# M900X.net
KiCad netlist of a schematic drawn in EAGLE
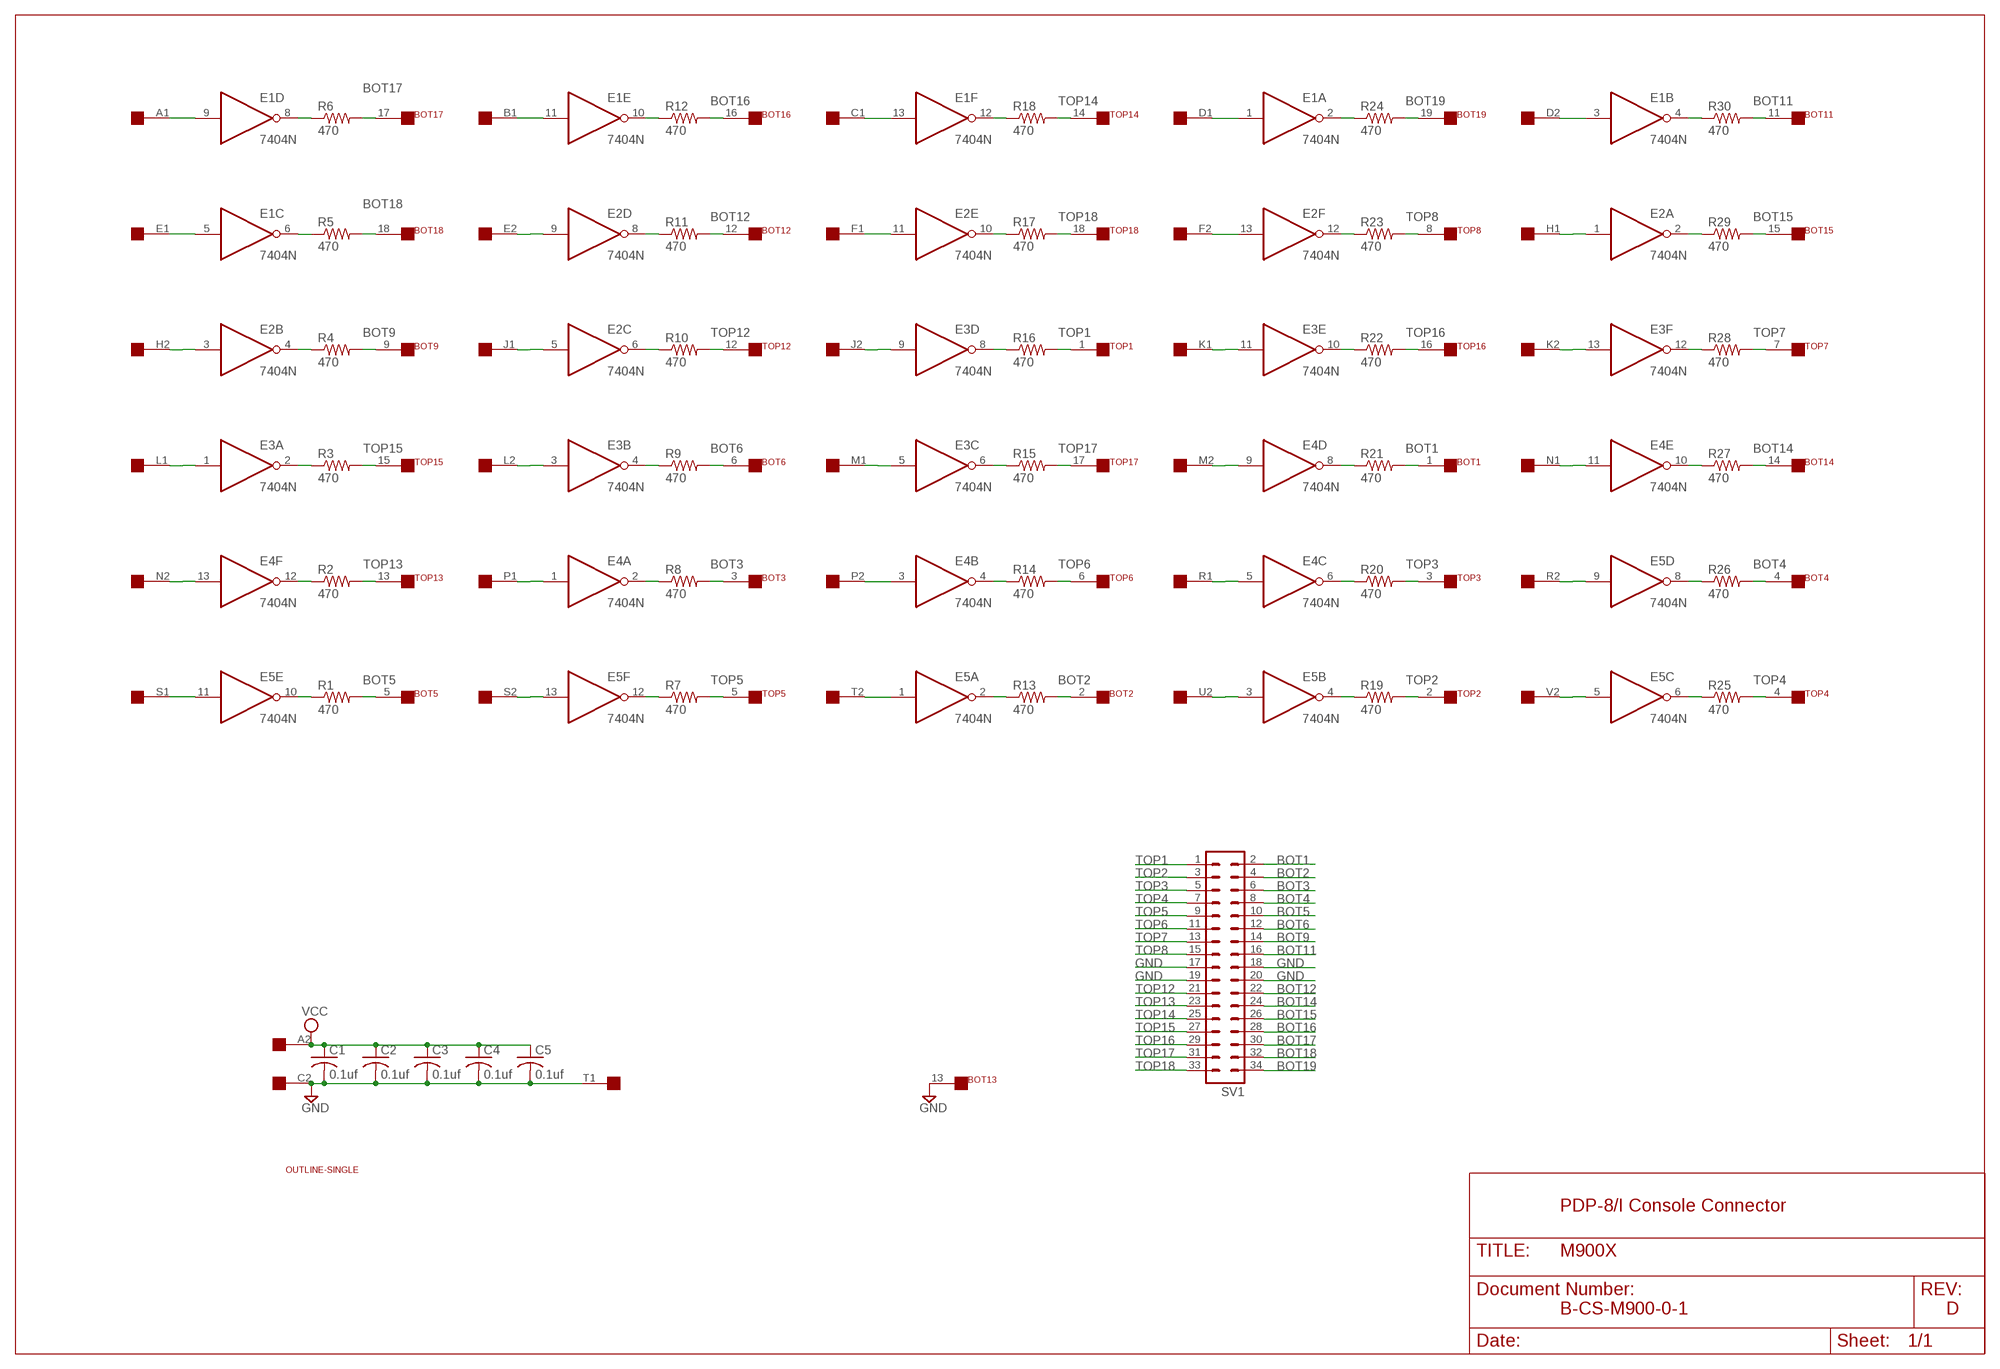
[diagram p0: schematic, sheet 1]

(export (version "E")
  (design (tool "Eeschema 10.0.6"))
  (components
    (comp (ref "BOT")
      (value "FLEX19")
      (footprint "eagle-import:FLEX19")
      (libsource (lib "eagle-import") (part "FLEX19"))
    )
    (comp (ref "C1")
      (value "0.1uf")
      (footprint "eagle-import:C050-025X075")
      (libsource (lib "eagle-import") (part "C-US050-025X075"))
    )
    (comp (ref "C2")
      (value "0.1uf")
      (footprint "eagle-import:C050-025X075")
      (libsource (lib "eagle-import") (part "C-US050-025X075"))
    )
    (comp (ref "C3")
      (value "0.1uf")
      (footprint "eagle-import:C050-025X075")
      (libsource (lib "eagle-import") (part "C-US050-025X075"))
    )
    (comp (ref "C4")
      (value "0.1uf")
      (footprint "eagle-import:C050-025X075")
      (libsource (lib "eagle-import") (part "C-US050-025X075"))
    )
    (comp (ref "C5")
      (value "0.1uf")
      (footprint "eagle-import:C050-025X075")
      (libsource (lib "eagle-import") (part "C-US050-025X075"))
    )
    (comp (ref "E1")
      (value "7404N")
      (footprint "eagle-import:DIL14")
      (libsource (lib "eagle-import") (part "7404N"))
    )
    (comp (ref "E2")
      (value "7404N")
      (footprint "eagle-import:DIL14")
      (libsource (lib "eagle-import") (part "7404N"))
    )
    (comp (ref "E3")
      (value "7404N")
      (footprint "eagle-import:DIL14")
      (libsource (lib "eagle-import") (part "7404N"))
    )
    (comp (ref "E4")
      (value "7404N")
      (footprint "eagle-import:DIL14")
      (libsource (lib "eagle-import") (part "7404N"))
    )
    (comp (ref "E5")
      (value "7404N")
      (footprint "eagle-import:DIL14")
      (libsource (lib "eagle-import") (part "7404N"))
    )
    (comp (ref "EDGE")
      (value "SINGLE")
      (footprint "eagle-import:EDGE-CON2")
      (libsource (lib "eagle-import") (part "SINGLE"))
    )
    (comp (ref "R1")
      (value "470")
      (footprint "eagle-import:0207_10")
      (libsource (lib "eagle-import") (part "R-US_0207/10"))
    )
    (comp (ref "R2")
      (value "470")
      (footprint "eagle-import:0207_10")
      (libsource (lib "eagle-import") (part "R-US_0207/10"))
    )
    (comp (ref "R3")
      (value "470")
      (footprint "eagle-import:0207_10")
      (libsource (lib "eagle-import") (part "R-US_0207/10"))
    )
    (comp (ref "R4")
      (value "470")
      (footprint "eagle-import:0207_10")
      (libsource (lib "eagle-import") (part "R-US_0207/10"))
    )
    (comp (ref "R5")
      (value "470")
      (footprint "eagle-import:0207_10")
      (libsource (lib "eagle-import") (part "R-US_0207/10"))
    )
    (comp (ref "R6")
      (value "470")
      (footprint "eagle-import:0207_10")
      (libsource (lib "eagle-import") (part "R-US_0207/10"))
    )
    (comp (ref "R7")
      (value "470")
      (footprint "eagle-import:0207_10")
      (libsource (lib "eagle-import") (part "R-US_0207/10"))
    )
    (comp (ref "R8")
      (value "470")
      (footprint "eagle-import:0207_10")
      (libsource (lib "eagle-import") (part "R-US_0207/10"))
    )
    (comp (ref "R9")
      (value "470")
      (footprint "eagle-import:0207_10")
      (libsource (lib "eagle-import") (part "R-US_0207/10"))
    )
    (comp (ref "R10")
      (value "470")
      (footprint "eagle-import:0207_10")
      (libsource (lib "eagle-import") (part "R-US_0207/10"))
    )
    (comp (ref "R11")
      (value "470")
      (footprint "eagle-import:0207_10")
      (libsource (lib "eagle-import") (part "R-US_0207/10"))
    )
    (comp (ref "R12")
      (value "470")
      (footprint "eagle-import:0207_10")
      (libsource (lib "eagle-import") (part "R-US_0207/10"))
    )
    (comp (ref "R13")
      (value "470")
      (footprint "eagle-import:0207_10")
      (libsource (lib "eagle-import") (part "R-US_0207/10"))
    )
    (comp (ref "R14")
      (value "470")
      (footprint "eagle-import:0207_10")
      (libsource (lib "eagle-import") (part "R-US_0207/10"))
    )
    (comp (ref "R15")
      (value "470")
      (footprint "eagle-import:0207_10")
      (libsource (lib "eagle-import") (part "R-US_0207/10"))
    )
    (comp (ref "R16")
      (value "470")
      (footprint "eagle-import:0207_10")
      (libsource (lib "eagle-import") (part "R-US_0207/10"))
    )
    (comp (ref "R17")
      (value "470")
      (footprint "eagle-import:0207_10")
      (libsource (lib "eagle-import") (part "R-US_0207/10"))
    )
    (comp (ref "R18")
      (value "470")
      (footprint "eagle-import:0207_10")
      (libsource (lib "eagle-import") (part "R-US_0207/10"))
    )
    (comp (ref "R19")
      (value "470")
      (footprint "eagle-import:0207_10")
      (libsource (lib "eagle-import") (part "R-US_0207/10"))
    )
    (comp (ref "R20")
      (value "470")
      (footprint "eagle-import:0207_10")
      (libsource (lib "eagle-import") (part "R-US_0207/10"))
    )
    (comp (ref "R21")
      (value "470")
      (footprint "eagle-import:0207_10")
      (libsource (lib "eagle-import") (part "R-US_0207/10"))
    )
    (comp (ref "R22")
      (value "470")
      (footprint "eagle-import:0207_10")
      (libsource (lib "eagle-import") (part "R-US_0207/10"))
    )
    (comp (ref "R23")
      (value "470")
      (footprint "eagle-import:0207_10")
      (libsource (lib "eagle-import") (part "R-US_0207/10"))
    )
    (comp (ref "R24")
      (value "470")
      (footprint "eagle-import:0207_10")
      (libsource (lib "eagle-import") (part "R-US_0207/10"))
    )
    (comp (ref "R25")
      (value "470")
      (footprint "eagle-import:0207_10")
      (libsource (lib "eagle-import") (part "R-US_0207/10"))
    )
    (comp (ref "R26")
      (value "470")
      (footprint "eagle-import:0207_10")
      (libsource (lib "eagle-import") (part "R-US_0207/10"))
    )
    (comp (ref "R27")
      (value "470")
      (footprint "eagle-import:0207_10")
      (libsource (lib "eagle-import") (part "R-US_0207/10"))
    )
    (comp (ref "R28")
      (value "470")
      (footprint "eagle-import:0207_10")
      (libsource (lib "eagle-import") (part "R-US_0207/10"))
    )
    (comp (ref "R29")
      (value "470")
      (footprint "eagle-import:0207_10")
      (libsource (lib "eagle-import") (part "R-US_0207/10"))
    )
    (comp (ref "R30")
      (value "470")
      (footprint "eagle-import:0207_10")
      (libsource (lib "eagle-import") (part "R-US_0207/10"))
    )
    (comp (ref "SV1")
      (value "ML34L")
      (footprint "eagle-import:ML34L")
      (libsource (lib "eagle-import") (part "ML34L"))
    )
    (comp (ref "TOP")
      (value "FLEX19")
      (footprint "eagle-import:FLEX19")
      (libsource (lib "eagle-import") (part "FLEX19"))
    )
    (comp (ref "U$2")
      (value "OUTLINE-SINGLE")
      (footprint "eagle-import:SINGLE")
      (libsource (lib "eagle-import") (part "OUTLINE-SINGLE"))
    )
  )
  (nets
    (net (code "1") (name "/BOT1") (class "Default")
      (node (ref "BOT") (pin "1") (pinfunction "1_1") (pintype "passive"))
      (node (ref "R21") (pin "2") (pinfunction "2_2") (pintype "passive"))
      (node (ref "SV1") (pin "2") (pinfunction "2_2") (pintype "passive"))
    )
    (net (code "2") (name "/BOT2") (class "Default")
      (node (ref "BOT") (pin "2") (pinfunction "1_2") (pintype "passive"))
      (node (ref "R13") (pin "2") (pinfunction "2_2") (pintype "passive"))
      (node (ref "SV1") (pin "4") (pinfunction "4_4") (pintype "passive"))
    )
    (net (code "3") (name "/BOT3") (class "Default")
      (node (ref "BOT") (pin "3") (pinfunction "1_3") (pintype "passive"))
      (node (ref "R8") (pin "2") (pinfunction "2_2") (pintype "passive"))
      (node (ref "SV1") (pin "6") (pinfunction "6_6") (pintype "passive"))
    )
    (net (code "4") (name "/BOT4") (class "Default")
      (node (ref "BOT") (pin "4") (pinfunction "1_4") (pintype "passive"))
      (node (ref "R26") (pin "2") (pinfunction "2_2") (pintype "passive"))
      (node (ref "SV1") (pin "8") (pinfunction "8_8") (pintype "passive"))
    )
    (net (code "5") (name "/BOT5") (class "Default")
      (node (ref "BOT") (pin "5") (pinfunction "1_5") (pintype "passive"))
      (node (ref "R1") (pin "2") (pinfunction "2_2") (pintype "passive"))
      (node (ref "SV1") (pin "10") (pinfunction "10_10") (pintype "passive"))
    )
    (net (code "6") (name "/BOT6") (class "Default")
      (node (ref "BOT") (pin "6") (pinfunction "1_6") (pintype "passive"))
      (node (ref "R9") (pin "2") (pinfunction "2_2") (pintype "passive"))
      (node (ref "SV1") (pin "12") (pinfunction "12_12") (pintype "passive"))
    )
    (net (code "7") (name "/BOT9") (class "Default")
      (node (ref "BOT") (pin "9") (pinfunction "1_9") (pintype "passive"))
      (node (ref "R4") (pin "2") (pinfunction "2_2") (pintype "passive"))
      (node (ref "SV1") (pin "14") (pinfunction "14_14") (pintype "passive"))
    )
    (net (code "8") (name "/BOT11") (class "Default")
      (node (ref "BOT") (pin "11") (pinfunction "1_11") (pintype "passive"))
      (node (ref "R30") (pin "2") (pinfunction "2_2") (pintype "passive"))
      (node (ref "SV1") (pin "16") (pinfunction "16_16") (pintype "passive"))
    )
    (net (code "9") (name "/BOT12") (class "Default")
      (node (ref "BOT") (pin "12") (pinfunction "1_12") (pintype "passive"))
      (node (ref "R11") (pin "2") (pinfunction "2_2") (pintype "passive"))
      (node (ref "SV1") (pin "22") (pinfunction "22_22") (pintype "passive"))
    )
    (net (code "10") (name "/BOT14") (class "Default")
      (node (ref "BOT") (pin "14") (pinfunction "1_14") (pintype "passive"))
      (node (ref "R27") (pin "2") (pinfunction "2_2") (pintype "passive"))
      (node (ref "SV1") (pin "24") (pinfunction "24_24") (pintype "passive"))
    )
    (net (code "11") (name "/BOT15") (class "Default")
      (node (ref "BOT") (pin "15") (pinfunction "1_15") (pintype "passive"))
      (node (ref "R29") (pin "2") (pinfunction "2_2") (pintype "passive"))
      (node (ref "SV1") (pin "26") (pinfunction "26_26") (pintype "passive"))
    )
    (net (code "12") (name "/BOT16") (class "Default")
      (node (ref "BOT") (pin "16") (pinfunction "1_16") (pintype "passive"))
      (node (ref "R12") (pin "2") (pinfunction "2_2") (pintype "passive"))
      (node (ref "SV1") (pin "28") (pinfunction "28_28") (pintype "passive"))
    )
    (net (code "13") (name "/BOT17") (class "Default")
      (node (ref "BOT") (pin "17") (pinfunction "1_17") (pintype "passive"))
      (node (ref "R6") (pin "2") (pinfunction "2_2") (pintype "passive"))
      (node (ref "SV1") (pin "30") (pinfunction "30_30") (pintype "passive"))
    )
    (net (code "14") (name "/BOT18") (class "Default")
      (node (ref "BOT") (pin "18") (pinfunction "1_18") (pintype "passive"))
      (node (ref "R5") (pin "2") (pinfunction "2_2") (pintype "passive"))
      (node (ref "SV1") (pin "32") (pinfunction "32_32") (pintype "passive"))
    )
    (net (code "15") (name "/BOT19") (class "Default")
      (node (ref "BOT") (pin "19") (pinfunction "1_19") (pintype "passive"))
      (node (ref "R24") (pin "2") (pinfunction "2_2") (pintype "passive"))
      (node (ref "SV1") (pin "34") (pinfunction "34_34") (pintype "passive"))
    )
    (net (code "16") (name "/TOP1") (class "Default")
      (node (ref "R16") (pin "2") (pinfunction "2_2") (pintype "passive"))
      (node (ref "SV1") (pin "1") (pinfunction "1_1") (pintype "passive"))
      (node (ref "TOP") (pin "1") (pinfunction "1_1") (pintype "passive"))
    )
    (net (code "17") (name "/TOP2") (class "Default")
      (node (ref "R19") (pin "2") (pinfunction "2_2") (pintype "passive"))
      (node (ref "SV1") (pin "3") (pinfunction "3_3") (pintype "passive"))
      (node (ref "TOP") (pin "2") (pinfunction "1_2") (pintype "passive"))
    )
    (net (code "18") (name "/TOP3") (class "Default")
      (node (ref "R20") (pin "2") (pinfunction "2_2") (pintype "passive"))
      (node (ref "SV1") (pin "5") (pinfunction "5_5") (pintype "passive"))
      (node (ref "TOP") (pin "3") (pinfunction "1_3") (pintype "passive"))
    )
    (net (code "19") (name "/TOP4") (class "Default")
      (node (ref "R25") (pin "2") (pinfunction "2_2") (pintype "passive"))
      (node (ref "SV1") (pin "7") (pinfunction "7_7") (pintype "passive"))
      (node (ref "TOP") (pin "4") (pinfunction "1_4") (pintype "passive"))
    )
    (net (code "20") (name "/TOP5") (class "Default")
      (node (ref "R7") (pin "2") (pinfunction "2_2") (pintype "passive"))
      (node (ref "SV1") (pin "9") (pinfunction "9_9") (pintype "passive"))
      (node (ref "TOP") (pin "5") (pinfunction "1_5") (pintype "passive"))
    )
    (net (code "21") (name "/TOP6") (class "Default")
      (node (ref "R14") (pin "2") (pinfunction "2_2") (pintype "passive"))
      (node (ref "SV1") (pin "11") (pinfunction "11_11") (pintype "passive"))
      (node (ref "TOP") (pin "6") (pinfunction "1_6") (pintype "passive"))
    )
    (net (code "22") (name "/TOP7") (class "Default")
      (node (ref "R28") (pin "2") (pinfunction "2_2") (pintype "passive"))
      (node (ref "SV1") (pin "13") (pinfunction "13_13") (pintype "passive"))
      (node (ref "TOP") (pin "7") (pinfunction "1_7") (pintype "passive"))
    )
    (net (code "23") (name "/TOP8") (class "Default")
      (node (ref "R23") (pin "2") (pinfunction "2_2") (pintype "passive"))
      (node (ref "SV1") (pin "15") (pinfunction "15_15") (pintype "passive"))
      (node (ref "TOP") (pin "8") (pinfunction "1_8") (pintype "passive"))
    )
    (net (code "24") (name "/TOP12") (class "Default")
      (node (ref "R10") (pin "2") (pinfunction "2_2") (pintype "passive"))
      (node (ref "SV1") (pin "21") (pinfunction "21_21") (pintype "passive"))
      (node (ref "TOP") (pin "12") (pinfunction "1_12") (pintype "passive"))
    )
    (net (code "25") (name "/TOP13") (class "Default")
      (node (ref "R2") (pin "2") (pinfunction "2_2") (pintype "passive"))
      (node (ref "SV1") (pin "23") (pinfunction "23_23") (pintype "passive"))
      (node (ref "TOP") (pin "13") (pinfunction "1_13") (pintype "passive"))
    )
    (net (code "26") (name "/TOP14") (class "Default")
      (node (ref "R18") (pin "2") (pinfunction "2_2") (pintype "passive"))
      (node (ref "SV1") (pin "25") (pinfunction "25_25") (pintype "passive"))
      (node (ref "TOP") (pin "14") (pinfunction "1_14") (pintype "passive"))
    )
    (net (code "27") (name "/TOP15") (class "Default")
      (node (ref "R3") (pin "2") (pinfunction "2_2") (pintype "passive"))
      (node (ref "SV1") (pin "27") (pinfunction "27_27") (pintype "passive"))
      (node (ref "TOP") (pin "15") (pinfunction "1_15") (pintype "passive"))
    )
    (net (code "28") (name "/TOP16") (class "Default")
      (node (ref "R22") (pin "2") (pinfunction "2_2") (pintype "passive"))
      (node (ref "SV1") (pin "29") (pinfunction "29_29") (pintype "passive"))
      (node (ref "TOP") (pin "16") (pinfunction "1_16") (pintype "passive"))
    )
    (net (code "29") (name "/TOP17") (class "Default")
      (node (ref "R15") (pin "2") (pinfunction "2_2") (pintype "passive"))
      (node (ref "SV1") (pin "31") (pinfunction "31_31") (pintype "passive"))
      (node (ref "TOP") (pin "17") (pinfunction "1_17") (pintype "passive"))
    )
    (net (code "30") (name "/TOP18") (class "Default")
      (node (ref "R17") (pin "2") (pinfunction "2_2") (pintype "passive"))
      (node (ref "SV1") (pin "33") (pinfunction "33_33") (pintype "passive"))
      (node (ref "TOP") (pin "18") (pinfunction "1_18") (pintype "passive"))
    )
    (net (code "31") (name "GND") (class "Default")
      (node (ref "BOT") (pin "13") (pinfunction "1_13") (pintype "passive"))
      (node (ref "C1") (pin "2") (pinfunction "2_2") (pintype "passive"))
      (node (ref "C2") (pin "2") (pinfunction "2_2") (pintype "passive"))
      (node (ref "C3") (pin "2") (pinfunction "2_2") (pintype "passive"))
      (node (ref "C4") (pin "2") (pinfunction "2_2") (pintype "passive"))
      (node (ref "C5") (pin "2") (pinfunction "2_2") (pintype "passive"))
      (node (ref "EDGE") (pin "C2") (pinfunction "1_C2") (pintype "bidirectional"))
      (node (ref "EDGE") (pin "T1") (pinfunction "1_T1") (pintype "bidirectional"))
      (node (ref "SV1") (pin "17") (pinfunction "17_17") (pintype "passive"))
      (node (ref "SV1") (pin "18") (pinfunction "18_18") (pintype "passive"))
      (node (ref "SV1") (pin "19") (pinfunction "19_19") (pintype "passive"))
      (node (ref "SV1") (pin "20") (pinfunction "20_20") (pintype "passive"))
    )
    (net (code "32") (name "Net-(E1A-I)") (class "Default")
      (node (ref "E1") (pin "1") (pinfunction "I_1") (pintype "input"))
      (node (ref "EDGE") (pin "D1") (pinfunction "1_D1") (pintype "bidirectional"))
    )
    (net (code "33") (name "Net-(E1A-O)") (class "Default")
      (node (ref "E1") (pin "2") (pinfunction "O_2") (pintype "output"))
      (node (ref "R24") (pin "1") (pinfunction "1_1") (pintype "passive"))
    )
    (net (code "34") (name "Net-(E1B-I)") (class "Default")
      (node (ref "E1") (pin "3") (pinfunction "I_3") (pintype "input"))
      (node (ref "EDGE") (pin "D2") (pinfunction "1_D2") (pintype "bidirectional"))
    )
    (net (code "35") (name "Net-(E1B-O)") (class "Default")
      (node (ref "E1") (pin "4") (pinfunction "O_4") (pintype "output"))
      (node (ref "R30") (pin "1") (pinfunction "1_1") (pintype "passive"))
    )
    (net (code "36") (name "Net-(E1C-I)") (class "Default")
      (node (ref "E1") (pin "5") (pinfunction "I_5") (pintype "input"))
      (node (ref "EDGE") (pin "E1") (pinfunction "1_E1") (pintype "bidirectional"))
    )
    (net (code "37") (name "Net-(E1C-O)") (class "Default")
      (node (ref "E1") (pin "6") (pinfunction "O_6") (pintype "output"))
      (node (ref "R5") (pin "1") (pinfunction "1_1") (pintype "passive"))
    )
    (net (code "38") (name "Net-(E1D-I)") (class "Default")
      (node (ref "E1") (pin "9") (pinfunction "I_9") (pintype "input"))
      (node (ref "EDGE") (pin "A1") (pinfunction "1_A1") (pintype "bidirectional"))
    )
    (net (code "39") (name "Net-(E1D-O)") (class "Default")
      (node (ref "E1") (pin "8") (pinfunction "O_8") (pintype "output"))
      (node (ref "R6") (pin "1") (pinfunction "1_1") (pintype "passive"))
    )
    (net (code "40") (name "Net-(E1E-I)") (class "Default")
      (node (ref "E1") (pin "11") (pinfunction "I_11") (pintype "input"))
      (node (ref "EDGE") (pin "B1") (pinfunction "1_B1") (pintype "bidirectional"))
    )
    (net (code "41") (name "Net-(E1E-O)") (class "Default")
      (node (ref "E1") (pin "10") (pinfunction "O_10") (pintype "output"))
      (node (ref "R12") (pin "1") (pinfunction "1_1") (pintype "passive"))
    )
    (net (code "42") (name "Net-(E1F-I)") (class "Default")
      (node (ref "E1") (pin "13") (pinfunction "I_13") (pintype "input"))
      (node (ref "EDGE") (pin "C1") (pinfunction "1_C1") (pintype "bidirectional"))
    )
    (net (code "43") (name "Net-(E1F-O)") (class "Default")
      (node (ref "E1") (pin "12") (pinfunction "O_12") (pintype "output"))
      (node (ref "R18") (pin "1") (pinfunction "1_1") (pintype "passive"))
    )
    (net (code "44") (name "Net-(E2A-I)") (class "Default")
      (node (ref "E2") (pin "1") (pinfunction "I_1") (pintype "input"))
      (node (ref "EDGE") (pin "H1") (pinfunction "1_H1") (pintype "bidirectional"))
    )
    (net (code "45") (name "Net-(E2A-O)") (class "Default")
      (node (ref "E2") (pin "2") (pinfunction "O_2") (pintype "output"))
      (node (ref "R29") (pin "1") (pinfunction "1_1") (pintype "passive"))
    )
    (net (code "46") (name "Net-(E2B-I)") (class "Default")
      (node (ref "E2") (pin "3") (pinfunction "I_3") (pintype "input"))
      (node (ref "EDGE") (pin "H2") (pinfunction "1_H2") (pintype "bidirectional"))
    )
    (net (code "47") (name "Net-(E2B-O)") (class "Default")
      (node (ref "E2") (pin "4") (pinfunction "O_4") (pintype "output"))
      (node (ref "R4") (pin "1") (pinfunction "1_1") (pintype "passive"))
    )
    (net (code "48") (name "Net-(E2C-I)") (class "Default")
      (node (ref "E2") (pin "5") (pinfunction "I_5") (pintype "input"))
      (node (ref "EDGE") (pin "J1") (pinfunction "1_J1") (pintype "bidirectional"))
    )
    (net (code "49") (name "Net-(E2C-O)") (class "Default")
      (node (ref "E2") (pin "6") (pinfunction "O_6") (pintype "output"))
      (node (ref "R10") (pin "1") (pinfunction "1_1") (pintype "passive"))
    )
    (net (code "50") (name "Net-(E2D-I)") (class "Default")
      (node (ref "E2") (pin "9") (pinfunction "I_9") (pintype "input"))
      (node (ref "EDGE") (pin "E2") (pinfunction "1_E2") (pintype "bidirectional"))
    )
    (net (code "51") (name "Net-(E2D-O)") (class "Default")
      (node (ref "E2") (pin "8") (pinfunction "O_8") (pintype "output"))
      (node (ref "R11") (pin "1") (pinfunction "1_1") (pintype "passive"))
    )
    (net (code "52") (name "Net-(E2E-I)") (class "Default")
      (node (ref "E2") (pin "11") (pinfunction "I_11") (pintype "input"))
      (node (ref "EDGE") (pin "F1") (pinfunction "1_F1") (pintype "bidirectional"))
    )
    (net (code "53") (name "Net-(E2E-O)") (class "Default")
      (node (ref "E2") (pin "10") (pinfunction "O_10") (pintype "output"))
      (node (ref "R17") (pin "1") (pinfunction "1_1") (pintype "passive"))
    )
    (net (code "54") (name "Net-(E2F-I)") (class "Default")
      (node (ref "E2") (pin "13") (pinfunction "I_13") (pintype "input"))
      (node (ref "EDGE") (pin "F2") (pinfunction "1_F2") (pintype "bidirectional"))
    )
    (net (code "55") (name "Net-(E2F-O)") (class "Default")
      (node (ref "E2") (pin "12") (pinfunction "O_12") (pintype "output"))
      (node (ref "R23") (pin "1") (pinfunction "1_1") (pintype "passive"))
    )
    (net (code "56") (name "Net-(E3A-I)") (class "Default")
      (node (ref "E3") (pin "1") (pinfunction "I_1") (pintype "input"))
      (node (ref "EDGE") (pin "L1") (pinfunction "1_L1") (pintype "bidirectional"))
    )
    (net (code "57") (name "Net-(E3A-O)") (class "Default")
      (node (ref "E3") (pin "2") (pinfunction "O_2") (pintype "output"))
      (node (ref "R3") (pin "1") (pinfunction "1_1") (pintype "passive"))
    )
    (net (code "58") (name "Net-(E3B-I)") (class "Default")
      (node (ref "E3") (pin "3") (pinfunction "I_3") (pintype "input"))
      (node (ref "EDGE") (pin "L2") (pinfunction "1_L2") (pintype "bidirectional"))
    )
    (net (code "59") (name "Net-(E3B-O)") (class "Default")
      (node (ref "E3") (pin "4") (pinfunction "O_4") (pintype "output"))
      (node (ref "R9") (pin "1") (pinfunction "1_1") (pintype "passive"))
    )
    (net (code "60") (name "Net-(E3C-I)") (class "Default")
      (node (ref "E3") (pin "5") (pinfunction "I_5") (pintype "input"))
      (node (ref "EDGE") (pin "M1") (pinfunction "1_M1") (pintype "bidirectional"))
    )
    (net (code "61") (name "Net-(E3C-O)") (class "Default")
      (node (ref "E3") (pin "6") (pinfunction "O_6") (pintype "output"))
      (node (ref "R15") (pin "1") (pinfunction "1_1") (pintype "passive"))
    )
    (net (code "62") (name "Net-(E3D-I)") (class "Default")
      (node (ref "E3") (pin "9") (pinfunction "I_9") (pintype "input"))
      (node (ref "EDGE") (pin "J2") (pinfunction "1_J2") (pintype "bidirectional"))
    )
    (net (code "63") (name "Net-(E3D-O)") (class "Default")
      (node (ref "E3") (pin "8") (pinfunction "O_8") (pintype "output"))
      (node (ref "R16") (pin "1") (pinfunction "1_1") (pintype "passive"))
    )
    (net (code "64") (name "Net-(E3E-I)") (class "Default")
      (node (ref "E3") (pin "11") (pinfunction "I_11") (pintype "input"))
      (node (ref "EDGE") (pin "K1") (pinfunction "1_K1") (pintype "bidirectional"))
    )
    (net (code "65") (name "Net-(E3E-O)") (class "Default")
      (node (ref "E3") (pin "10") (pinfunction "O_10") (pintype "output"))
      (node (ref "R22") (pin "1") (pinfunction "1_1") (pintype "passive"))
    )
    (net (code "66") (name "Net-(E3F-I)") (class "Default")
      (node (ref "E3") (pin "13") (pinfunction "I_13") (pintype "input"))
      (node (ref "EDGE") (pin "K2") (pinfunction "1_K2") (pintype "bidirectional"))
    )
    (net (code "67") (name "Net-(E3F-O)") (class "Default")
      (node (ref "E3") (pin "12") (pinfunction "O_12") (pintype "output"))
      (node (ref "R28") (pin "1") (pinfunction "1_1") (pintype "passive"))
    )
    (net (code "68") (name "Net-(E4A-I)") (class "Default")
      (node (ref "E4") (pin "1") (pinfunction "I_1") (pintype "input"))
      (node (ref "EDGE") (pin "P1") (pinfunction "1_P1") (pintype "bidirectional"))
    )
    (net (code "69") (name "Net-(E4A-O)") (class "Default")
      (node (ref "E4") (pin "2") (pinfunction "O_2") (pintype "output"))
      (node (ref "R8") (pin "1") (pinfunction "1_1") (pintype "passive"))
    )
    (net (code "70") (name "Net-(E4B-I)") (class "Default")
      (node (ref "E4") (pin "3") (pinfunction "I_3") (pintype "input"))
      (node (ref "EDGE") (pin "P2") (pinfunction "1_P2") (pintype "bidirectional"))
    )
    (net (code "71") (name "Net-(E4B-O)") (class "Default")
      (node (ref "E4") (pin "4") (pinfunction "O_4") (pintype "output"))
      (node (ref "R14") (pin "1") (pinfunction "1_1") (pintype "passive"))
    )
    (net (code "72") (name "Net-(E4C-I)") (class "Default")
      (node (ref "E4") (pin "5") (pinfunction "I_5") (pintype "input"))
      (node (ref "EDGE") (pin "R1") (pinfunction "1_R1") (pintype "bidirectional"))
    )
    (net (code "73") (name "Net-(E4C-O)") (class "Default")
      (node (ref "E4") (pin "6") (pinfunction "O_6") (pintype "output"))
      (node (ref "R20") (pin "1") (pinfunction "1_1") (pintype "passive"))
    )
    (net (code "74") (name "Net-(E4D-I)") (class "Default")
      (node (ref "E4") (pin "9") (pinfunction "I_9") (pintype "input"))
      (node (ref "EDGE") (pin "M2") (pinfunction "1_M2") (pintype "bidirectional"))
    )
    (net (code "75") (name "Net-(E4D-O)") (class "Default")
      (node (ref "E4") (pin "8") (pinfunction "O_8") (pintype "output"))
      (node (ref "R21") (pin "1") (pinfunction "1_1") (pintype "passive"))
    )
    (net (code "76") (name "Net-(E4E-I)") (class "Default")
      (node (ref "E4") (pin "11") (pinfunction "I_11") (pintype "input"))
      (node (ref "EDGE") (pin "N1") (pinfunction "1_N1") (pintype "bidirectional"))
    )
    (net (code "77") (name "Net-(E4E-O)") (class "Default")
      (node (ref "E4") (pin "10") (pinfunction "O_10") (pintype "output"))
      (node (ref "R27") (pin "1") (pinfunction "1_1") (pintype "passive"))
    )
    (net (code "78") (name "Net-(E4F-I)") (class "Default")
      (node (ref "E4") (pin "13") (pinfunction "I_13") (pintype "input"))
      (node (ref "EDGE") (pin "N2") (pinfunction "1_N2") (pintype "bidirectional"))
    )
    (net (code "79") (name "Net-(E4F-O)") (class "Default")
      (node (ref "E4") (pin "12") (pinfunction "O_12") (pintype "output"))
      (node (ref "R2") (pin "1") (pinfunction "1_1") (pintype "passive"))
    )
    (net (code "80") (name "Net-(E5A-I)") (class "Default")
      (node (ref "E5") (pin "1") (pinfunction "I_1") (pintype "input"))
      (node (ref "EDGE") (pin "T2") (pinfunction "1_T2") (pintype "bidirectional"))
    )
    (net (code "81") (name "Net-(E5A-O)") (class "Default")
      (node (ref "E5") (pin "2") (pinfunction "O_2") (pintype "output"))
      (node (ref "R13") (pin "1") (pinfunction "1_1") (pintype "passive"))
    )
    (net (code "82") (name "Net-(E5B-I)") (class "Default")
      (node (ref "E5") (pin "3") (pinfunction "I_3") (pintype "input"))
      (node (ref "EDGE") (pin "U2") (pinfunction "1_U2") (pintype "bidirectional"))
    )
    (net (code "83") (name "Net-(E5B-O)") (class "Default")
      (node (ref "E5") (pin "4") (pinfunction "O_4") (pintype "output"))
      (node (ref "R19") (pin "1") (pinfunction "1_1") (pintype "passive"))
    )
    (net (code "84") (name "Net-(E5C-I)") (class "Default")
      (node (ref "E5") (pin "5") (pinfunction "I_5") (pintype "input"))
      (node (ref "EDGE") (pin "V2") (pinfunction "1_V2") (pintype "bidirectional"))
    )
    (net (code "85") (name "Net-(E5C-O)") (class "Default")
      (node (ref "E5") (pin "6") (pinfunction "O_6") (pintype "output"))
      (node (ref "R25") (pin "1") (pinfunction "1_1") (pintype "passive"))
    )
    (net (code "86") (name "Net-(E5D-I)") (class "Default")
      (node (ref "E5") (pin "9") (pinfunction "I_9") (pintype "input"))
      (node (ref "EDGE") (pin "R2") (pinfunction "1_R2") (pintype "bidirectional"))
    )
    (net (code "87") (name "Net-(E5D-O)") (class "Default")
      (node (ref "E5") (pin "8") (pinfunction "O_8") (pintype "output"))
      (node (ref "R26") (pin "1") (pinfunction "1_1") (pintype "passive"))
    )
    (net (code "88") (name "Net-(E5E-I)") (class "Default")
      (node (ref "E5") (pin "11") (pinfunction "I_11") (pintype "input"))
      (node (ref "EDGE") (pin "S1") (pinfunction "1_S1") (pintype "bidirectional"))
    )
    (net (code "89") (name "Net-(E5E-O)") (class "Default")
      (node (ref "E5") (pin "10") (pinfunction "O_10") (pintype "output"))
      (node (ref "R1") (pin "1") (pinfunction "1_1") (pintype "passive"))
    )
    (net (code "90") (name "Net-(E5F-I)") (class "Default")
      (node (ref "E5") (pin "13") (pinfunction "I_13") (pintype "input"))
      (node (ref "EDGE") (pin "S2") (pinfunction "1_S2") (pintype "bidirectional"))
    )
    (net (code "91") (name "Net-(E5F-O)") (class "Default")
      (node (ref "E5") (pin "12") (pinfunction "O_12") (pintype "output"))
      (node (ref "R7") (pin "1") (pinfunction "1_1") (pintype "passive"))
    )
    (net (code "92") (name "VCC") (class "Default")
      (node (ref "C1") (pin "1") (pinfunction "1_1") (pintype "passive"))
      (node (ref "C2") (pin "1") (pinfunction "1_1") (pintype "passive"))
      (node (ref "C3") (pin "1") (pinfunction "1_1") (pintype "passive"))
      (node (ref "C4") (pin "1") (pinfunction "1_1") (pintype "passive"))
      (node (ref "C5") (pin "1") (pinfunction "1_1") (pintype "passive"))
      (node (ref "EDGE") (pin "A2") (pinfunction "1_A2") (pintype "bidirectional"))
    )
  )
)
